# Schematic_v51.net
KiCad netlist of a schematic drawn in EAGLE
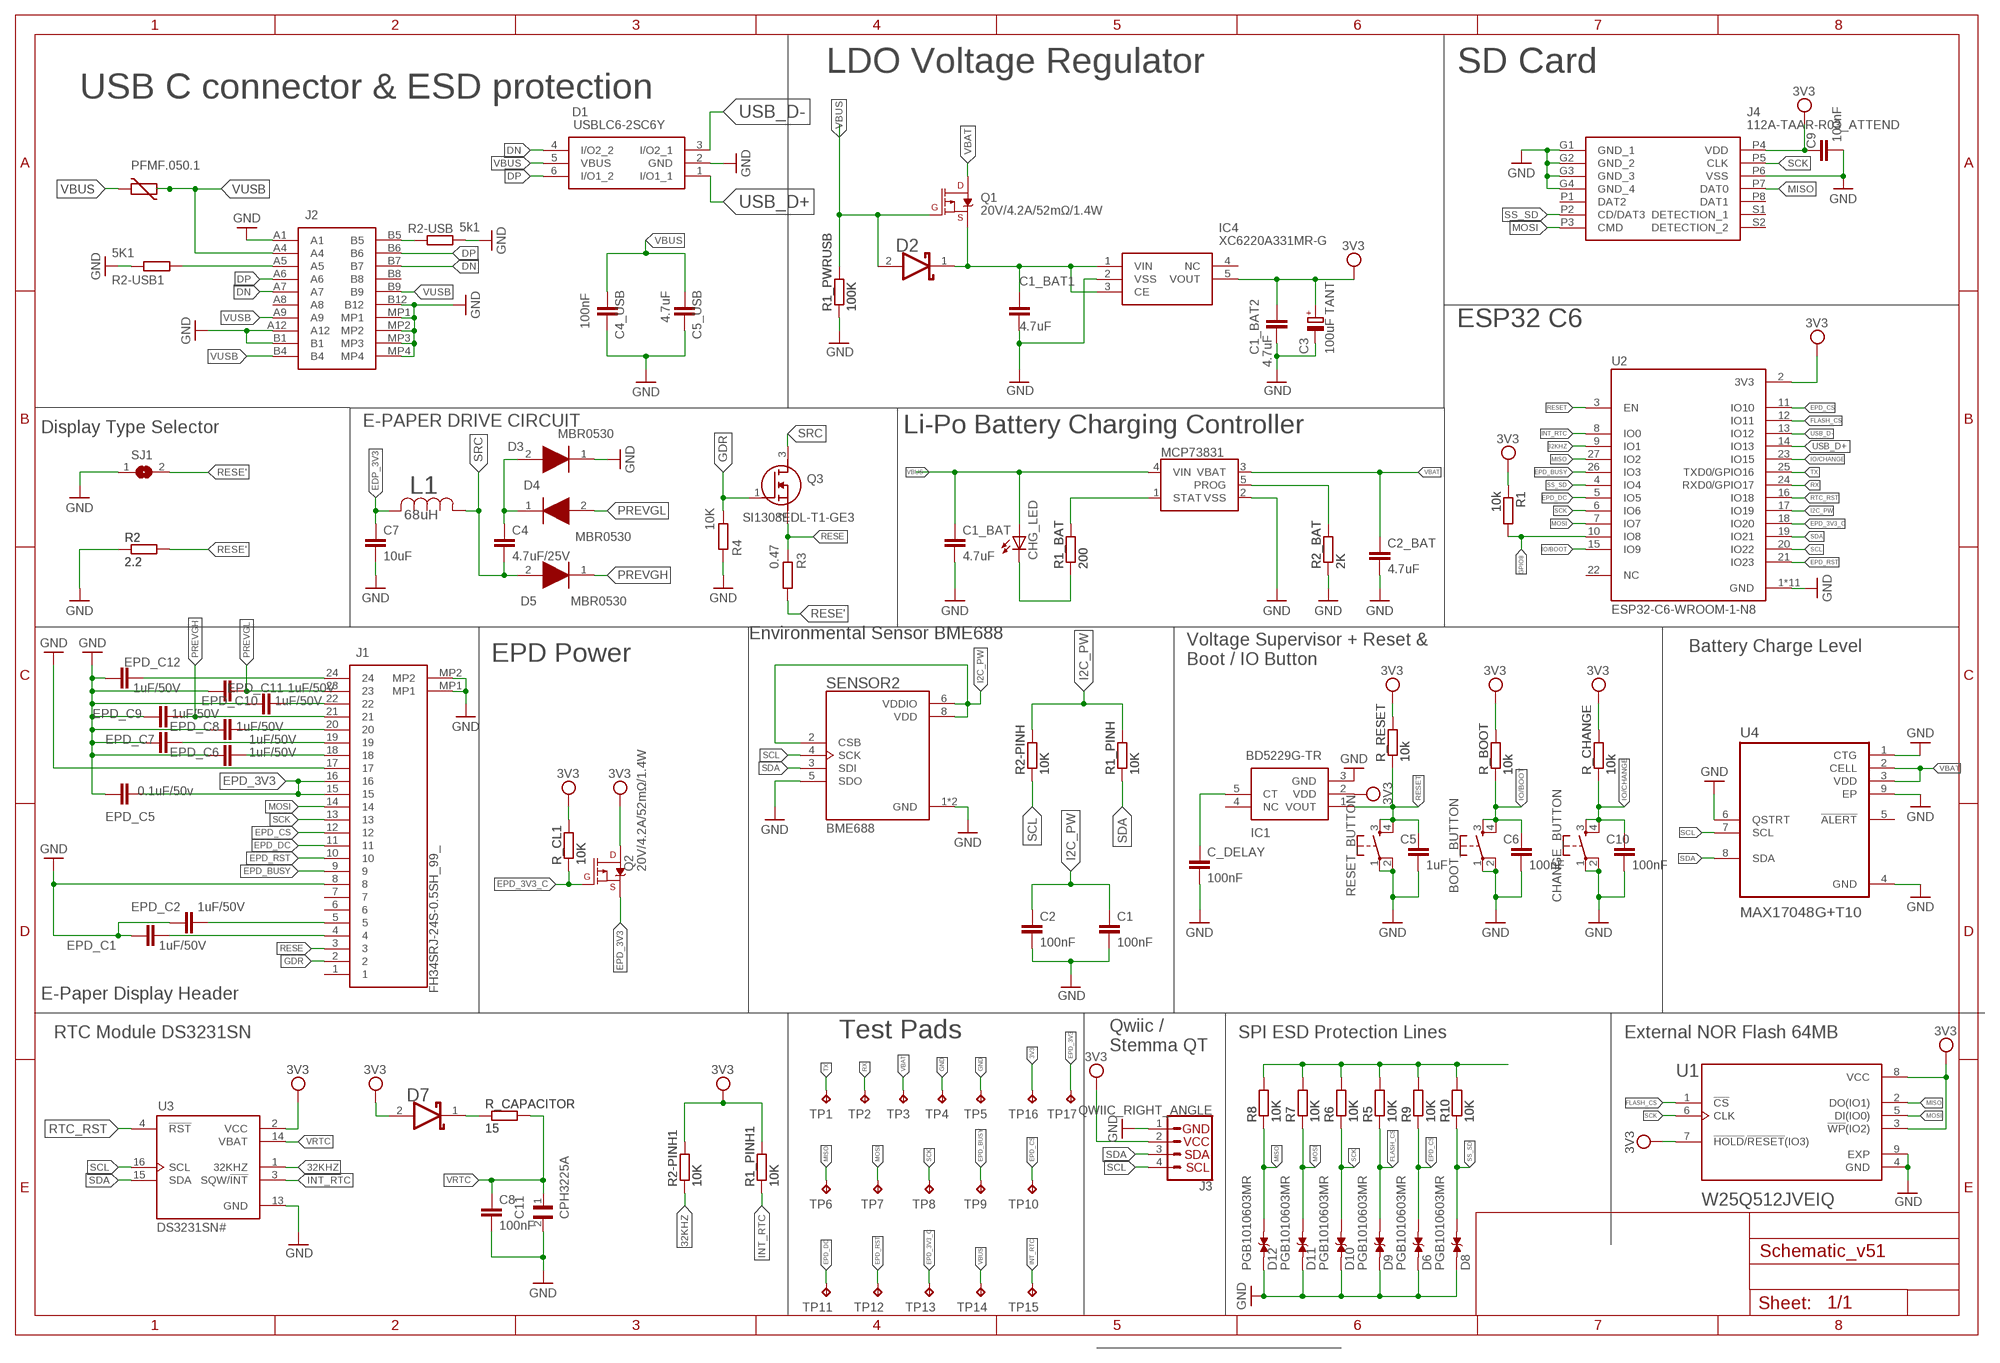
[diagram p0: schematic, sheet 1]

(export (version "E")
  (design (tool "Eeschema 10.0.6"))
  (components
    (comp (ref "BOOT_BUTTON")
      (value "BUTTON_CUSYOMV1")
      (footprint "eagle-import:MYBUTTON")
      (libsource (lib "eagle-import") (part "BUTTON_CUSYOMV1"))
    )
    (comp (ref "C1")
      (value "100nF")
      (footprint "eagle-import:EAGLE-LTSPICE_C0402")
      (libsource (lib "eagle-import") (part "EAGLE-LTSPICE_CC0402"))
    )
    (comp (ref "C1_BAT")
      (value "4.7uF")
      (footprint "eagle-import:EAGLE-LTSPICE_C0402")
      (libsource (lib "eagle-import") (part "EAGLE-LTSPICE_CC0402"))
    )
    (comp (ref "C1_BAT1")
      (value "4.7uF")
      (footprint "eagle-import:ESP32_WROVER_EAGLE-LTSPICE_C0402")
      (libsource (lib "eagle-import") (part "ESP32_WROVER_EAGLE-LTSPICE_CC0402"))
    )
    (comp (ref "C1_BAT2")
      (value "4.7uF")
      (footprint "eagle-import:ESP32_WROVER_EAGLE-LTSPICE_C0402")
      (libsource (lib "eagle-import") (part "ESP32_WROVER_EAGLE-LTSPICE_CC0402"))
    )
    (comp (ref "C2")
      (value "100nF")
      (footprint "eagle-import:EAGLE-LTSPICE_C0402")
      (libsource (lib "eagle-import") (part "EAGLE-LTSPICE_CC0402"))
    )
    (comp (ref "C2_BAT")
      (value "4.7uF")
      (footprint "eagle-import:EAGLE-LTSPICE_C0402")
      (libsource (lib "eagle-import") (part "EAGLE-LTSPICE_CC0402"))
    )
    (comp (ref "C3")
      (value "100uF TANT")
      (footprint "eagle-import:RCL_CT3528")
      (libsource (lib "eagle-import") (part "RCL_CPOL-EUCT3528"))
    )
    (comp (ref "C4")
      (value "4.7uF/25V")
      (footprint "eagle-import:EAGLE-LTSPICE_C0402")
      (libsource (lib "eagle-import") (part "EAGLE-LTSPICE_CC0402"))
    )
    (comp (ref "C4_USB")
      (value "100nF")
      (footprint "eagle-import:EAGLE-LTSPICE_C0402")
      (libsource (lib "eagle-import") (part "EAGLE-LTSPICE_CC0402"))
    )
    (comp (ref "C5")
      (value "1uF")
      (footprint "eagle-import:EAGLE-LTSPICE_C0402")
      (libsource (lib "eagle-import") (part "EAGLE-LTSPICE_CC0402"))
    )
    (comp (ref "C5_USB")
      (value "4.7uF")
      (footprint "eagle-import:EAGLE-LTSPICE_C0402")
      (libsource (lib "eagle-import") (part "EAGLE-LTSPICE_CC0402"))
    )
    (comp (ref "C6")
      (value "100nF")
      (footprint "eagle-import:EAGLE-LTSPICE_C0402")
      (libsource (lib "eagle-import") (part "EAGLE-LTSPICE_CC0402"))
    )
    (comp (ref "C7")
      (value "10uF")
      (footprint "eagle-import:EAGLE-LTSPICE_C0402")
      (libsource (lib "eagle-import") (part "EAGLE-LTSPICE_CC0402"))
    )
    (comp (ref "C8")
      (value "100nF")
      (footprint "eagle-import:EAGLE-LTSPICE_C0402")
      (libsource (lib "eagle-import") (part "EAGLE-LTSPICE_CC0402"))
    )
    (comp (ref "C9")
      (value "100nF")
      (footprint "eagle-import:EAGLE-LTSPICE_C0402")
      (libsource (lib "eagle-import") (part "EAGLE-LTSPICE_CC0402"))
    )
    (comp (ref "C10")
      (value "100nF")
      (footprint "eagle-import:EAGLE-LTSPICE_C0402")
      (libsource (lib "eagle-import") (part "EAGLE-LTSPICE_CC0402"))
    )
    (comp (ref "C11")
      (value "CPH3225A")
      (footprint "eagle-import:CAPCP3225X100N")
      (fields (field (name "MF") "Seiko Instruments"))
      (libsource (lib "eagle-import") (part "CPH3225A"))
    )
    (comp (ref "CHANGE_BUTTON")
      (value "BUTTON_CUSYOMV1")
      (footprint "eagle-import:MYBUTTON")
      (libsource (lib "eagle-import") (part "BUTTON_CUSYOMV1"))
    )
    (comp (ref "CHG_LED")
      (value "ADAFRUIT_LEDCHIP-LED0603")
      (footprint "eagle-import:ADAFRUIT_CHIP-LED0603")
      (libsource (lib "eagle-import") (part "ADAFRUIT_LEDCHIP-LED0603"))
    )
    (comp (ref "C_DELAY")
      (value "100nF")
      (footprint "eagle-import:EAGLE-LTSPICE_C0402")
      (libsource (lib "eagle-import") (part "EAGLE-LTSPICE_CC0402"))
    )
    (comp (ref "D1")
      (value "USBLC6-2SC6Y")
      (footprint "eagle-import:SOT95P280X145-6N")
      (fields (field (name "MF") "STMicroelectronics"))
      (libsource (lib "eagle-import") (part "USBLC6-2SC6Y"))
    )
    (comp (ref "D2")
      (value "ESP32_WROVER_AVX---SD0805S020S1R0_AVX_SD0805S020S1R0_0_0AVX_SD0805S020S1R0_0_0")
      (footprint "eagle-import:ESP32_WROVER_AVX---SD0805S020S1R0_AVX_SD0805S020S1R0_0")
      (fields
        (field (name "DIGIKEY_PART_NUMBER") "478-7800-1-ND")
        (field (name "MF") "AVX")
        (field (name "MOUSER_PART_NUMBER") "581-SD0805S020S1R0")
      )
      (libsource (lib "eagle-import") (part "ESP32_WROVER_AVX---SD0805S020S1R0_AVX_SD0805S020S1R0_0_0AVX_SD0805S020S1R0_0_0"))
    )
    (comp (ref "D3")
      (value "MBR0530")
      (footprint "eagle-import:SOD3716X135N")
      (fields (field (name "MF") "ON Semiconductor"))
      (libsource (lib "eagle-import") (part "MBR0530"))
    )
    (comp (ref "D4")
      (value "MBR0530")
      (footprint "eagle-import:SOD3716X135N")
      (fields (field (name "MF") "ON Semiconductor"))
      (libsource (lib "eagle-import") (part "MBR0530"))
    )
    (comp (ref "D5")
      (value "MBR0530")
      (footprint "eagle-import:SOD3716X135N")
      (fields (field (name "MF") "ON Semiconductor"))
      (libsource (lib "eagle-import") (part "MBR0530"))
    )
    (comp (ref "D6")
      (value "PGB1010603MR")
      (footprint "eagle-import:DIOC1608X36N")
      (fields (field (name "MF") "Littelfuse Inc."))
      (libsource (lib "eagle-import") (part "PGB1010603MR"))
    )
    (comp (ref "D7")
      (value "ESP32_WROVER_AVX---SD0805S020S1R0_AVX_SD0805S020S1R0_0_0AVX_SD0805S020S1R0_0_0")
      (footprint "eagle-import:ESP32_WROVER_AVX---SD0805S020S1R0_AVX_SD0805S020S1R0_0")
      (fields
        (field (name "DIGIKEY_PART_NUMBER") "478-7800-1-ND")
        (field (name "MF") "AVX")
        (field (name "MOUSER_PART_NUMBER") "581-SD0805S020S1R0")
      )
      (libsource (lib "eagle-import") (part "ESP32_WROVER_AVX---SD0805S020S1R0_AVX_SD0805S020S1R0_0_0AVX_SD0805S020S1R0_0_0"))
    )
    (comp (ref "D8")
      (value "PGB1010603MR")
      (footprint "eagle-import:DIOC1608X36N")
      (fields (field (name "MF") "Littelfuse Inc."))
      (libsource (lib "eagle-import") (part "PGB1010603MR"))
    )
    (comp (ref "D9")
      (value "PGB1010603MR")
      (footprint "eagle-import:DIOC1608X36N")
      (fields (field (name "MF") "Littelfuse Inc."))
      (libsource (lib "eagle-import") (part "PGB1010603MR"))
    )
    (comp (ref "D10")
      (value "PGB1010603MR")
      (footprint "eagle-import:DIOC1608X36N")
      (fields (field (name "MF") "Littelfuse Inc."))
      (libsource (lib "eagle-import") (part "PGB1010603MR"))
    )
    (comp (ref "D11")
      (value "PGB1010603MR")
      (footprint "eagle-import:DIOC1608X36N")
      (fields (field (name "MF") "Littelfuse Inc."))
      (libsource (lib "eagle-import") (part "PGB1010603MR"))
    )
    (comp (ref "D12")
      (value "PGB1010603MR")
      (footprint "eagle-import:DIOC1608X36N")
      (fields (field (name "MF") "Littelfuse Inc."))
      (libsource (lib "eagle-import") (part "PGB1010603MR"))
    )
    (comp (ref "EPD_C1")
      (value "1uF/50V")
      (footprint "eagle-import:EAGLE-LTSPICE_C0402")
      (libsource (lib "eagle-import") (part "EAGLE-LTSPICE_CC0402"))
    )
    (comp (ref "EPD_C2")
      (value "1uF/50V")
      (footprint "eagle-import:EAGLE-LTSPICE_C0402")
      (libsource (lib "eagle-import") (part "EAGLE-LTSPICE_CC0402"))
    )
    (comp (ref "EPD_C5")
      (value "0.1uF/50v")
      (footprint "eagle-import:EAGLE-LTSPICE_C0402")
      (libsource (lib "eagle-import") (part "EAGLE-LTSPICE_CC0402"))
    )
    (comp (ref "EPD_C6")
      (value "1uF/50V")
      (footprint "eagle-import:EAGLE-LTSPICE_C0402")
      (libsource (lib "eagle-import") (part "EAGLE-LTSPICE_CC0402"))
    )
    (comp (ref "EPD_C7")
      (value "1uF/50V")
      (footprint "eagle-import:EAGLE-LTSPICE_C0402")
      (libsource (lib "eagle-import") (part "EAGLE-LTSPICE_CC0402"))
    )
    (comp (ref "EPD_C8")
      (value "1uF/50V")
      (footprint "eagle-import:EAGLE-LTSPICE_C0402")
      (libsource (lib "eagle-import") (part "EAGLE-LTSPICE_CC0402"))
    )
    (comp (ref "EPD_C9")
      (value "1uF/50V")
      (footprint "eagle-import:EAGLE-LTSPICE_C0402")
      (libsource (lib "eagle-import") (part "EAGLE-LTSPICE_CC0402"))
    )
    (comp (ref "EPD_C10")
      (value "1uF/50V")
      (footprint "eagle-import:EAGLE-LTSPICE_C0402")
      (libsource (lib "eagle-import") (part "EAGLE-LTSPICE_CC0402"))
    )
    (comp (ref "EPD_C11")
      (value "1uF/50V")
      (footprint "eagle-import:EAGLE-LTSPICE_C0402")
      (libsource (lib "eagle-import") (part "EAGLE-LTSPICE_CC0402"))
    )
    (comp (ref "EPD_C12")
      (value "1uF/50V")
      (footprint "eagle-import:EAGLE-LTSPICE_C0402")
      (libsource (lib "eagle-import") (part "EAGLE-LTSPICE_CC0402"))
    )
    (comp (ref "IC1")
      (value "BD5229G-TR")
      (footprint "eagle-import:SOT95P280X125-5N")
      (fields (field (name "MOUSER_PART_NUMBER") "755-BD5229G-TR"))
      (libsource (lib "eagle-import") (part "BD5229G-TR"))
    )
    (comp (ref "IC4")
      (value "XC6220A331MR-G")
      (footprint "eagle-import:SOT95P280X120-5N")
      (fields (field (name "MOUSER_PART_NUMBER") "865-XC6220A331MR-G"))
      (libsource (lib "eagle-import") (part "XC6220A331MR-G"))
    )
    (comp (ref "J1")
      (value "FH34SRJ-24S-0.5SH_99_")
      (footprint "eagle-import:FH34SRJ24S05SH99")
      (fields
        (field (name "MANUFACTURER_PART_NUMBER") "FH34SRJ-24S-0.5SH(99)")
        (field (name "MOUSER_PART_NUMBER") "798-FH34SRJ24S05SH99")
      )
      (libsource (lib "eagle-import") (part "FH34SRJ-24S-0.5SH_99_"))
    )
    (comp (ref "J2")
      (value "SAMACSYS_PARTS_USB4110-GF-A")
      (footprint "eagle-import:SAMACSYS_PARTS_USB4110GFA")
      (fields
        (field (name "MANUFACTURER_PART_NUMBER") "USB4110-GF-A")
        (field (name "MOUSER_PART_NUMBER") "640-USB4110-GF-A")
      )
      (libsource (lib "eagle-import") (part "SAMACSYS_PARTS_USB4110-GF-A"))
    )
    (comp (ref "J3")
      (value "QWIIC_RIGHT_ANGLE")
      (footprint "eagle-import:JST04_1MM_RA")
      (libsource (lib "eagle-import") (part "QWIIC_CONNECTORJS-1MM"))
    )
    (comp (ref "J4")
      (value "112A-TAAR-R03_ATTEND")
      (footprint "eagle-import:112ATAARR03ATTEND")
      (fields (field (name "MANUFACTURER_PART_NUMBER") "112A-TAAR-R03 ATTEND"))
      (libsource (lib "eagle-import") (part "112A-TAAR-R03_ATTEND"))
    )
    (comp (ref "L1")
      (value "68uH")
      (footprint "eagle-import:IND_4828-WE-TPC_WRE")
      (fields
        (field (name "MANUFACTURER_PART_NUMBER") "744043680")
        (field (name "COPYRIGHT") "Copyright (C) 2024 Ultra Librarian. All rights reserved.")
      )
      (libsource (lib "eagle-import") (part "744043680IND_4828-WE-TPC_WRE"))
    )
    (comp (ref "MCP73831")
      (value "ESP32_WROVER_SPARKFUN-IC-POWER_MCP73831")
      (footprint "eagle-import:ESP32_WROVER_SPARKFUN-IC-POWER_SOT23-5")
      (libsource (lib "eagle-import") (part "ESP32_WROVER_SPARKFUN-IC-POWER_MCP73831"))
    )
    (comp (ref "PFMF.050.1")
      (value "ESP32C6_VARISTORCN1812")
      (footprint "eagle-import:ESP32C6_VARISTOR_CT_CN1812")
      (libsource (lib "eagle-import") (part "ESP32C6_VARISTORCN1812"))
    )
    (comp (ref "Q1")
      (value "20V/4.2A/52mΩ/1.4W")
      (footprint "eagle-import:ESP32_WROVER_SPARKFUN-DISCRETESEMI_SOT23-3")
      (libsource (lib "eagle-import") (part "ESP32_WROVER_SPARKFUN-DISCRETESEMI_MOSFET_PCH-DMG2305UX-7"))
    )
    (comp (ref "Q2")
      (value "20V/4.2A/52mΩ/1.4W")
      (footprint "eagle-import:ESP32_WROVER_SPARKFUN-DISCRETESEMI_SOT23-3")
      (libsource (lib "eagle-import") (part "ESP32_WROVER_SPARKFUN-DISCRETESEMI_MOSFET_PCH-DMG2305UX-7"))
    )
    (comp (ref "Q3")
      (value "SI1308EDL-T1-GE3")
      (footprint "eagle-import:SOT65P210X110-3N")
      (fields (field (name "MF") "Vishay Siliconix"))
      (libsource (lib "eagle-import") (part "SI1308EDL-T1-GE3"))
    )
    (comp (ref "R1")
      (value "10k")
      (footprint "eagle-import:ESP32_WROVER_EAGLE-LTSPICE_R0402")
      (libsource (lib "eagle-import") (part "ESP32_WROVER_EAGLE-LTSPICE_RR0402"))
    )
    (comp (ref "R1_BAT")
      (value "200")
      (footprint "eagle-import:ESP32_WROVER_EAGLE-LTSPICE_R0402")
      (libsource (lib "eagle-import") (part "ESP32_WROVER_EAGLE-LTSPICE_RR0402"))
    )
    (comp (ref "R1_PINH")
      (value "10K")
      (footprint "eagle-import:ESP32_WROVER_EAGLE-LTSPICE_R0402")
      (libsource (lib "eagle-import") (part "ESP32_WROVER_EAGLE-LTSPICE_RR0402"))
    )
    (comp (ref "R1_PINH1")
      (value "10K")
      (footprint "eagle-import:ESP32_WROVER_EAGLE-LTSPICE_R0402")
      (libsource (lib "eagle-import") (part "ESP32_WROVER_EAGLE-LTSPICE_RR0402"))
    )
    (comp (ref "R1_PWRUSB")
      (value "100K")
      (footprint "eagle-import:ESP32_WROVER_EAGLE-LTSPICE_R0402")
      (libsource (lib "eagle-import") (part "ESP32_WROVER_EAGLE-LTSPICE_RR0402"))
    )
    (comp (ref "R2")
      (value "2.2")
      (footprint "eagle-import:ESP32_WROVER_EAGLE-LTSPICE_R0402")
      (libsource (lib "eagle-import") (part "ESP32_WROVER_EAGLE-LTSPICE_RR0402"))
    )
    (comp (ref "R2-PINH")
      (value "10K")
      (footprint "eagle-import:ESP32_WROVER_EAGLE-LTSPICE_R0402")
      (libsource (lib "eagle-import") (part "ESP32_WROVER_EAGLE-LTSPICE_RR0402"))
    )
    (comp (ref "R2-PINH1")
      (value "10K")
      (footprint "eagle-import:ESP32_WROVER_EAGLE-LTSPICE_R0402")
      (libsource (lib "eagle-import") (part "ESP32_WROVER_EAGLE-LTSPICE_RR0402"))
    )
    (comp (ref "R2-USB")
      (value "5k1")
      (footprint "eagle-import:ESP32_WROVER_EAGLE-LTSPICE_R0402")
      (libsource (lib "eagle-import") (part "ESP32_WROVER_EAGLE-LTSPICE_RR0402"))
    )
    (comp (ref "R2-USB1")
      (value "5K1")
      (footprint "eagle-import:ESP32_WROVER_EAGLE-LTSPICE_R0402")
      (fields (field (name "SPICEPREFIX") "R2-USB1"))
      (libsource (lib "eagle-import") (part "ESP32_WROVER_EAGLE-LTSPICE_RR0402"))
    )
    (comp (ref "R2_BAT")
      (value "2K")
      (footprint "eagle-import:ESP32_WROVER_EAGLE-LTSPICE_R0402")
      (libsource (lib "eagle-import") (part "ESP32_WROVER_EAGLE-LTSPICE_RR0402"))
    )
    (comp (ref "R3")
      (value "0.47")
      (footprint "eagle-import:ESP32_WROVER_EAGLE-LTSPICE_R0402")
      (libsource (lib "eagle-import") (part "ESP32_WROVER_EAGLE-LTSPICE_RR0402"))
    )
    (comp (ref "R4")
      (value "10K")
      (footprint "eagle-import:ESP32_WROVER_EAGLE-LTSPICE_R0402")
      (libsource (lib "eagle-import") (part "ESP32_WROVER_EAGLE-LTSPICE_RR0402"))
    )
    (comp (ref "R5")
      (value "10K")
      (footprint "eagle-import:ESP32_WROVER_EAGLE-LTSPICE_R0402")
      (libsource (lib "eagle-import") (part "ESP32_WROVER_EAGLE-LTSPICE_RR0402"))
    )
    (comp (ref "R6")
      (value "10K")
      (footprint "eagle-import:ESP32_WROVER_EAGLE-LTSPICE_R0402")
      (libsource (lib "eagle-import") (part "ESP32_WROVER_EAGLE-LTSPICE_RR0402"))
    )
    (comp (ref "R7")
      (value "10K")
      (footprint "eagle-import:ESP32_WROVER_EAGLE-LTSPICE_R0402")
      (libsource (lib "eagle-import") (part "ESP32_WROVER_EAGLE-LTSPICE_RR0402"))
    )
    (comp (ref "R8")
      (value "10K")
      (footprint "eagle-import:ESP32_WROVER_EAGLE-LTSPICE_R0402")
      (libsource (lib "eagle-import") (part "ESP32_WROVER_EAGLE-LTSPICE_RR0402"))
    )
    (comp (ref "R9")
      (value "10K")
      (footprint "eagle-import:ESP32_WROVER_EAGLE-LTSPICE_R0402")
      (libsource (lib "eagle-import") (part "ESP32_WROVER_EAGLE-LTSPICE_RR0402"))
    )
    (comp (ref "R10")
      (value "10K")
      (footprint "eagle-import:ESP32_WROVER_EAGLE-LTSPICE_R0402")
      (libsource (lib "eagle-import") (part "ESP32_WROVER_EAGLE-LTSPICE_RR0402"))
    )
    (comp (ref "RESET_BUTTON")
      (value "BUTTON_CUSYOMV1")
      (footprint "eagle-import:MYBUTTON")
      (libsource (lib "eagle-import") (part "BUTTON_CUSYOMV1"))
    )
    (comp (ref "R_BOOT")
      (value "10k")
      (footprint "eagle-import:ESP32_WROVER_EAGLE-LTSPICE_R0402")
      (libsource (lib "eagle-import") (part "ESP32_WROVER_EAGLE-LTSPICE_RR0402"))
    )
    (comp (ref "R_CAPACITOR")
      (value "15")
      (footprint "eagle-import:ESP32_WROVER_EAGLE-LTSPICE_R0402")
      (libsource (lib "eagle-import") (part "ESP32_WROVER_EAGLE-LTSPICE_RR0402"))
    )
    (comp (ref "R_CHANGE")
      (value "10k")
      (footprint "eagle-import:ESP32_WROVER_EAGLE-LTSPICE_R0402")
      (libsource (lib "eagle-import") (part "ESP32_WROVER_EAGLE-LTSPICE_RR0402"))
    )
    (comp (ref "R_CL1")
      (value "10K")
      (footprint "eagle-import:ESP32_WROVER_EAGLE-LTSPICE_R0402")
      (libsource (lib "eagle-import") (part "ESP32_WROVER_EAGLE-LTSPICE_RR0402"))
    )
    (comp (ref "R_RESET")
      (value "10k")
      (footprint "eagle-import:ESP32_WROVER_EAGLE-LTSPICE_R0402")
      (libsource (lib "eagle-import") (part "ESP32_WROVER_EAGLE-LTSPICE_RR0402"))
    )
    (comp (ref "SENSOR2")
      (value "ESP32_WROVER_BME680_BME680")
      (footprint "eagle-import:ESP32_WROVER_BME680_PSON80P300X300X100-8N")
      (fields (field (name "MF") "Bosch Sensortec") (field (name "MP") "BME680"))
      (libsource (lib "eagle-import") (part "ESP32_WROVER_BME680_BME680"))
    )
    (comp (ref "SJ1") (value "SJ") (footprint "eagle-import:SJ") (libsource (lib "eagle-import") (part "SJ")))
    (comp (ref "TP1")
      (value "TPTP20R")
      (footprint "eagle-import:TP20R")
      (libsource (lib "eagle-import") (part "TPTP20R"))
    )
    (comp (ref "TP2")
      (value "TPTP20R")
      (footprint "eagle-import:TP20R")
      (libsource (lib "eagle-import") (part "TPTP20R"))
    )
    (comp (ref "TP3")
      (value "TPTP20R")
      (footprint "eagle-import:TP20R")
      (libsource (lib "eagle-import") (part "TPTP20R"))
    )
    (comp (ref "TP4")
      (value "TPTP20R")
      (footprint "eagle-import:TP20R")
      (libsource (lib "eagle-import") (part "TPTP20R"))
    )
    (comp (ref "TP5")
      (value "TPTP20R")
      (footprint "eagle-import:TP20R")
      (libsource (lib "eagle-import") (part "TPTP20R"))
    )
    (comp (ref "TP6")
      (value "TPTP20R")
      (footprint "eagle-import:TP20R")
      (libsource (lib "eagle-import") (part "TPTP20R"))
    )
    (comp (ref "TP7")
      (value "TPTP20R")
      (footprint "eagle-import:TP20R")
      (libsource (lib "eagle-import") (part "TPTP20R"))
    )
    (comp (ref "TP8")
      (value "TPTP20R")
      (footprint "eagle-import:TP20R")
      (libsource (lib "eagle-import") (part "TPTP20R"))
    )
    (comp (ref "TP9")
      (value "TPTP20R")
      (footprint "eagle-import:TP20R")
      (libsource (lib "eagle-import") (part "TPTP20R"))
    )
    (comp (ref "TP10")
      (value "TPTP20R")
      (footprint "eagle-import:TP20R")
      (libsource (lib "eagle-import") (part "TPTP20R"))
    )
    (comp (ref "TP11")
      (value "TPTP20R")
      (footprint "eagle-import:TP20R")
      (libsource (lib "eagle-import") (part "TPTP20R"))
    )
    (comp (ref "TP12")
      (value "TPTP20R")
      (footprint "eagle-import:TP20R")
      (libsource (lib "eagle-import") (part "TPTP20R"))
    )
    (comp (ref "TP13")
      (value "TPTP20R")
      (footprint "eagle-import:TP20R")
      (libsource (lib "eagle-import") (part "TPTP20R"))
    )
    (comp (ref "TP14")
      (value "TPTP20R")
      (footprint "eagle-import:TP20R")
      (libsource (lib "eagle-import") (part "TPTP20R"))
    )
    (comp (ref "TP15")
      (value "TPTP20R")
      (footprint "eagle-import:TP20R")
      (libsource (lib "eagle-import") (part "TPTP20R"))
    )
    (comp (ref "TP16")
      (value "TPTP20R")
      (footprint "eagle-import:TP20R")
      (libsource (lib "eagle-import") (part "TPTP20R"))
    )
    (comp (ref "TP17")
      (value "TPTP20R")
      (footprint "eagle-import:TP20R")
      (libsource (lib "eagle-import") (part "TPTP20R"))
    )
    (comp (ref "U1")
      (value "W25Q512JVEIQ")
      (footprint "eagle-import:SON127P600X800X80-9N")
      (fields (field (name "MF") "Winbond Electronics"))
      (libsource (lib "eagle-import") (part "W25Q512JVEIQ"))
    )
    (comp (ref "U2")
      (value "ESP32-C6-WROOM-1-N8")
      (footprint "eagle-import:XCVR_ESP32-C6-WROOM-1-N8")
      (fields (field (name "MF") "Espressif Systems"))
      (libsource (lib "eagle-import") (part "ESP32-C6-WROOM-1-N8"))
    )
    (comp (ref "U3")
      (value "DS3231SN#")
      (footprint "eagle-import:SOIC127P1032X265-16N")
      (fields (field (name "MF") "Analog Devices"))
      (libsource (lib "eagle-import") (part "DS3231SN#"))
    )
    (comp (ref "U4")
      (value "MAX17048G+T10")
      (footprint "eagle-import:SON50P200X200X80-9N")
      (fields (field (name "MF") "Analog Devices"))
      (libsource (lib "eagle-import") (part "MAX17048G+T10"))
    )
  )
  (nets
    (net (code "1") (name "3V3") (class "Default")
      (node (ref "C1_BAT2") (pin "1") (pinfunction "1_1") (pintype "passive"))
      (node (ref "C3") (pin "+") (pinfunction "+_+") (pintype "passive"))
      (node (ref "C9") (pin "2") (pinfunction "2_2") (pintype "passive"))
      (node (ref "D7") (pin "2") (pinfunction "ANODE_2") (pintype "bidirectional"))
      (node (ref "IC1") (pin "2") (pinfunction "VDD_2") (pintype "bidirectional"))
      (node (ref "IC4") (pin "5") (pinfunction "VOUT_5") (pintype "bidirectional"))
      (node (ref "J3") (pin "2") (pinfunction "2_2") (pintype "power_in"))
      (node (ref "J4") (pin "P4") (pinfunction "VDD_P4") (pintype "bidirectional"))
      (node (ref "Q2") (pin "3") (pinfunction "D_3") (pintype "bidirectional"))
      (node (ref "R1") (pin "1") (pinfunction "1_1") (pintype "passive"))
      (node (ref "R1_PINH1") (pin "2") (pinfunction "2_2") (pintype "passive"))
      (node (ref "R2-PINH1") (pin "2") (pinfunction "2_2") (pintype "passive"))
      (node (ref "R_BOOT") (pin "2") (pinfunction "2_2") (pintype "passive"))
      (node (ref "R_CHANGE") (pin "2") (pinfunction "2_2") (pintype "passive"))
      (node (ref "R_CL1") (pin "2") (pinfunction "2_2") (pintype "passive"))
      (node (ref "R_RESET") (pin "2") (pinfunction "2_2") (pintype "passive"))
      (node (ref "TP16") (pin "TP") (pinfunction "TP_TP") (pintype "input"))
      (node (ref "U1") (pin "3") (pinfunction "~{WP}(IO2)_3") (pintype "bidirectional"))
      (node (ref "U1") (pin "7") (pinfunction "~{HOLD}/~{RESET}(IO3)_7") (pintype "bidirectional"))
      (node (ref "U1") (pin "8") (pinfunction "VCC_8") (pintype "power_in"))
      (node (ref "U2") (pin "2") (pinfunction "3V3_2") (pintype "power_in"))
      (node (ref "U3") (pin "2") (pinfunction "VCC_2") (pintype "power_in"))
    )
    (net (code "2") (name "32KHZ") (class "Default")
      (node (ref "R2-PINH1") (pin "1") (pinfunction "1_1") (pintype "passive"))
      (node (ref "U2") (pin "9") (pinfunction "IO1_9") (pintype "bidirectional"))
      (node (ref "U3") (pin "1") (pinfunction "32KHZ_1") (pintype "output"))
    )
    (net (code "3") (name "DN") (class "Default")
      (node (ref "D1") (pin "4") (pinfunction "I/O2_2_4") (pintype "bidirectional"))
      (node (ref "J2") (pin "A7") (pinfunction "A7_A7") (pintype "bidirectional"))
      (node (ref "J2") (pin "B7") (pinfunction "B7_B7") (pintype "bidirectional"))
    )
    (net (code "4") (name "DP") (class "Default")
      (node (ref "D1") (pin "6") (pinfunction "I/O1_2_6") (pintype "bidirectional"))
      (node (ref "J2") (pin "A6") (pinfunction "A6_A6") (pintype "bidirectional"))
      (node (ref "J2") (pin "B6") (pinfunction "B6_B6") (pintype "bidirectional"))
    )
    (net (code "5") (name "EDP_3V3") (class "Default")
      (node (ref "C7") (pin "1") (pinfunction "1_1") (pintype "passive"))
      (node (ref "L1") (pin "2") (pinfunction "2_2") (pintype "passive"))
    )
    (net (code "6") (name "EPD_3V3") (class "Default")
      (node (ref "EPD_C5") (pin "2") (pinfunction "2_2") (pintype "passive"))
      (node (ref "J1") (pin "15") (pinfunction "15_15") (pintype "bidirectional"))
      (node (ref "J1") (pin "16") (pinfunction "16_16") (pintype "bidirectional"))
      (node (ref "Q2") (pin "2") (pinfunction "S_2") (pintype "bidirectional"))
      (node (ref "TP17") (pin "TP") (pinfunction "TP_TP") (pintype "input"))
    )
    (net (code "7") (name "EPD_3V3_C") (class "Default")
      (node (ref "Q2") (pin "1") (pinfunction "G_1") (pintype "bidirectional"))
      (node (ref "R_CL1") (pin "1") (pinfunction "1_1") (pintype "passive"))
      (node (ref "TP13") (pin "TP") (pinfunction "TP_TP") (pintype "input"))
      (node (ref "U2") (pin "18") (pinfunction "IO20_18") (pintype "bidirectional"))
    )
    (net (code "8") (name "EPD_BUSY") (class "Default")
      (node (ref "J1") (pin "9") (pinfunction "9_9") (pintype "bidirectional"))
      (node (ref "TP9") (pin "TP") (pinfunction "TP_TP") (pintype "input"))
      (node (ref "U2") (pin "26") (pinfunction "IO3_26") (pintype "bidirectional"))
    )
    (net (code "9") (name "EPD_CS") (class "Default")
      (node (ref "D6") (pin "2") (pinfunction "2_2") (pintype "passive"))
      (node (ref "J1") (pin "12") (pinfunction "12_12") (pintype "bidirectional"))
      (node (ref "R9") (pin "1") (pinfunction "1_1") (pintype "passive"))
      (node (ref "TP10") (pin "TP") (pinfunction "TP_TP") (pintype "input"))
      (node (ref "U2") (pin "11") (pinfunction "IO10_11") (pintype "bidirectional"))
    )
    (net (code "10") (name "EPD_DC") (class "Default")
      (node (ref "J1") (pin "11") (pinfunction "11_11") (pintype "bidirectional"))
      (node (ref "TP11") (pin "TP") (pinfunction "TP_TP") (pintype "input"))
      (node (ref "U2") (pin "5") (pinfunction "IO5_5") (pintype "bidirectional"))
    )
    (net (code "11") (name "EPD_RST") (class "Default")
      (node (ref "J1") (pin "10") (pinfunction "10_10") (pintype "bidirectional"))
      (node (ref "TP12") (pin "TP") (pinfunction "TP_TP") (pintype "input"))
      (node (ref "U2") (pin "21") (pinfunction "IO23_21") (pintype "bidirectional"))
    )
    (net (code "12") (name "FLASH_CS") (class "Default")
      (node (ref "D9") (pin "2") (pinfunction "2_2") (pintype "passive"))
      (node (ref "R5") (pin "1") (pinfunction "1_1") (pintype "passive"))
      (node (ref "U1") (pin "1") (pinfunction "~{CS}_1") (pintype "input"))
      (node (ref "U2") (pin "12") (pinfunction "IO11_12") (pintype "bidirectional"))
    )
    (net (code "13") (name "GDR") (class "Default")
      (node (ref "J1") (pin "2") (pinfunction "2_2") (pintype "bidirectional"))
      (node (ref "Q3") (pin "1") (pinfunction "G_1") (pintype "bidirectional"))
      (node (ref "R4") (pin "2") (pinfunction "2_2") (pintype "passive"))
    )
    (net (code "14") (name "GND") (class "Default")
      (node (ref "BOOT_BUTTON") (pin "1") (pinfunction "1_1") (pintype "passive"))
      (node (ref "BOOT_BUTTON") (pin "2") (pinfunction "2_2") (pintype "passive"))
      (node (ref "C1") (pin "2") (pinfunction "2_2") (pintype "passive"))
      (node (ref "C10") (pin "2") (pinfunction "2_2") (pintype "passive"))
      (node (ref "C11") (pin "2") (pinfunction "2_2") (pintype "passive"))
      (node (ref "C1_BAT") (pin "2") (pinfunction "2_2") (pintype "passive"))
      (node (ref "C1_BAT1") (pin "2") (pinfunction "2_2") (pintype "passive"))
      (node (ref "C1_BAT2") (pin "2") (pinfunction "2_2") (pintype "passive"))
      (node (ref "C2") (pin "2") (pinfunction "2_2") (pintype "passive"))
      (node (ref "C2_BAT") (pin "2") (pinfunction "2_2") (pintype "passive"))
      (node (ref "C3") (pin "-") (pinfunction "-_-") (pintype "passive"))
      (node (ref "C4_USB") (pin "2") (pinfunction "2_2") (pintype "passive"))
      (node (ref "C5") (pin "2") (pinfunction "2_2") (pintype "passive"))
      (node (ref "C5_USB") (pin "2") (pinfunction "2_2") (pintype "passive"))
      (node (ref "C6") (pin "2") (pinfunction "2_2") (pintype "passive"))
      (node (ref "C7") (pin "2") (pinfunction "2_2") (pintype "passive"))
      (node (ref "C8") (pin "2") (pinfunction "2_2") (pintype "passive"))
      (node (ref "C9") (pin "1") (pinfunction "1_1") (pintype "passive"))
      (node (ref "CHANGE_BUTTON") (pin "1") (pinfunction "1_1") (pintype "passive"))
      (node (ref "CHANGE_BUTTON") (pin "2") (pinfunction "2_2") (pintype "passive"))
      (node (ref "C_DELAY") (pin "2") (pinfunction "2_2") (pintype "passive"))
      (node (ref "D1") (pin "2") (pinfunction "GND_2") (pintype "bidirectional"))
      (node (ref "D10") (pin "1") (pinfunction "1_1") (pintype "passive"))
      (node (ref "D11") (pin "1") (pinfunction "1_1") (pintype "passive"))
      (node (ref "D12") (pin "1") (pinfunction "1_1") (pintype "passive"))
      (node (ref "D3") (pin "1") (pinfunction "K_1") (pintype "bidirectional"))
      (node (ref "D6") (pin "1") (pinfunction "1_1") (pintype "passive"))
      (node (ref "D8") (pin "1") (pinfunction "1_1") (pintype "passive"))
      (node (ref "D9") (pin "1") (pinfunction "1_1") (pintype "passive"))
      (node (ref "EPD_C1") (pin "1") (pinfunction "1_1") (pintype "passive"))
      (node (ref "EPD_C10") (pin "1") (pinfunction "1_1") (pintype "passive"))
      (node (ref "EPD_C11") (pin "1") (pinfunction "1_1") (pintype "passive"))
      (node (ref "EPD_C12") (pin "1") (pinfunction "1_1") (pintype "passive"))
      (node (ref "EPD_C2") (pin "1") (pinfunction "1_1") (pintype "passive"))
      (node (ref "EPD_C5") (pin "1") (pinfunction "1_1") (pintype "passive"))
      (node (ref "EPD_C6") (pin "1") (pinfunction "1_1") (pintype "passive"))
      (node (ref "EPD_C7") (pin "1") (pinfunction "1_1") (pintype "passive"))
      (node (ref "EPD_C8") (pin "1") (pinfunction "1_1") (pintype "passive"))
      (node (ref "EPD_C9") (pin "1") (pinfunction "1_1") (pintype "passive"))
      (node (ref "IC1") (pin "3") (pinfunction "GND_3") (pintype "bidirectional"))
      (node (ref "IC4") (pin "2") (pinfunction "VSS_2") (pintype "bidirectional"))
      (node (ref "J1") (pin "17") (pinfunction "17_17") (pintype "bidirectional"))
      (node (ref "J1") (pin "8") (pinfunction "8_8") (pintype "bidirectional"))
      (node (ref "J1") (pin "MP1") (pinfunction "MP1_MP1") (pintype "bidirectional"))
      (node (ref "J1") (pin "MP2") (pinfunction "MP2_MP2") (pintype "bidirectional"))
      (node (ref "J2") (pin "A1") (pinfunction "A1_A1") (pintype "bidirectional"))
      (node (ref "J2") (pin "A12") (pinfunction "A12_A12") (pintype "bidirectional"))
      (node (ref "J2") (pin "B1") (pinfunction "B1_B1") (pintype "bidirectional"))
      (node (ref "J2") (pin "B12") (pinfunction "B12_B12") (pintype "bidirectional"))
      (node (ref "J2") (pin "MP1") (pinfunction "MP1_MP1") (pintype "bidirectional"))
      (node (ref "J2") (pin "MP2") (pinfunction "MP2_MP2") (pintype "bidirectional"))
      (node (ref "J2") (pin "MP3") (pinfunction "MP3_MP3") (pintype "bidirectional"))
      (node (ref "J2") (pin "MP4") (pinfunction "MP4_MP4") (pintype "bidirectional"))
      (node (ref "J3") (pin "1") (pinfunction "1_1") (pintype "power_in"))
      (node (ref "J4") (pin "G1") (pinfunction "GND_1_G1") (pintype "bidirectional"))
      (node (ref "J4") (pin "G2") (pinfunction "GND_2_G2") (pintype "bidirectional"))
      (node (ref "J4") (pin "G3") (pinfunction "GND_3_G3") (pintype "bidirectional"))
      (node (ref "J4") (pin "G4") (pinfunction "GND_4_G4") (pintype "bidirectional"))
      (node (ref "J4") (pin "P6") (pinfunction "VSS_P6") (pintype "bidirectional"))
      (node (ref "MCP73831") (pin "2") (pinfunction "VSS_2") (pintype "power_in"))
      (node (ref "R1_PWRUSB") (pin "1") (pinfunction "1_1") (pintype "passive"))
      (node (ref "R2") (pin "1") (pinfunction "1_1") (pintype "passive"))
      (node (ref "R2-USB") (pin "2") (pinfunction "2_2") (pintype "passive"))
      (node (ref "R2-USB1") (pin "1") (pinfunction "1_1") (pintype "passive"))
      (node (ref "R2_BAT") (pin "1") (pinfunction "1_1") (pintype "passive"))
      (node (ref "R4") (pin "1") (pinfunction "1_1") (pintype "passive"))
      (node (ref "RESET_BUTTON") (pin "1") (pinfunction "1_1") (pintype "passive"))
      (node (ref "RESET_BUTTON") (pin "2") (pinfunction "2_2") (pintype "passive"))
      (node (ref "SENSOR2") (pin "1") (pinfunction "GND_1") (pintype "power_in"))
      (node (ref "SENSOR2") (pin "5") (pinfunction "SDO_5") (pintype "bidirectional"))
      (node (ref "SENSOR2") (pin "7") (pinfunction "GND_7") (pintype "power_in"))
      (node (ref "SJ1") (pin "1") (pinfunction "1_1") (pintype "passive"))
      (node (ref "TP4") (pin "TP") (pinfunction "TP_TP") (pintype "input"))
      (node (ref "TP5") (pin "TP") (pinfunction "TP_TP") (pintype "input"))
      (node (ref "U1") (pin "4") (pinfunction "GND_4") (pintype "power_in"))
      (node (ref "U1") (pin "9") (pinfunction "EXP_9") (pintype "passive"))
      (node (ref "U2") (pin "1") (pinfunction "GND_1") (pintype "power_in"))
      (node (ref "U2") (pin "28") (pinfunction "GND_28") (pintype "power_in"))
      (node (ref "U2") (pin "29_1") (pinfunction "GND_29_1") (pintype "power_in"))
      (node (ref "U2") (pin "29_2") (pinfunction "GND_29_2") (pintype "power_in"))
      (node (ref "U2") (pin "29_3") (pinfunction "GND_29_3") (pintype "power_in"))
      (node (ref "U2") (pin "29_4") (pinfunction "GND_29_4") (pintype "power_in"))
      (node (ref "U2") (pin "29_5") (pinfunction "GND_29_5") (pintype "power_in"))
      (node (ref "U2") (pin "29_6") (pinfunction "GND_29_6") (pintype "power_in"))
      (node (ref "U2") (pin "29_7") (pinfunction "GND_29_7") (pintype "power_in"))
      (node (ref "U2") (pin "29_8") (pinfunction "GND_29_8") (pintype "power_in"))
      (node (ref "U2") (pin "29_9") (pinfunction "GND_29_9") (pintype "power_in"))
      (node (ref "U3") (pin "13") (pinfunction "GND_13") (pintype "power_in"))
      (node (ref "U4") (pin "1") (pinfunction "CTG_1") (pintype "power_in"))
      (node (ref "U4") (pin "4") (pinfunction "GND_4") (pintype "power_in"))
      (node (ref "U4") (pin "6") (pinfunction "QSTRT_6") (pintype "input"))
      (node (ref "U4") (pin "9") (pinfunction "EP_9") (pintype "power_in"))
    )
    (net (code "15") (name "GPIO8") (class "Default")
      (node (ref "R1") (pin "2") (pinfunction "2_2") (pintype "passive"))
      (node (ref "U2") (pin "10") (pinfunction "IO8_10") (pintype "bidirectional"))
    )
    (net (code "16") (name "I2C_PW") (class "Default")
      (node (ref "C1") (pin "1") (pinfunction "1_1") (pintype "passive"))
      (node (ref "C2") (pin "1") (pinfunction "1_1") (pintype "passive"))
      (node (ref "R1_PINH") (pin "2") (pinfunction "2_2") (pintype "passive"))
      (node (ref "R2-PINH") (pin "2") (pinfunction "2_2") (pintype "passive"))
      (node (ref "SENSOR2") (pin "2") (pinfunction "CSB_2") (pintype "input"))
      (node (ref "SENSOR2") (pin "6") (pinfunction "VDDIO_6") (pintype "power_in"))
      (node (ref "SENSOR2") (pin "8") (pinfunction "VDD_8") (pintype "power_in"))
      (node (ref "U2") (pin "17") (pinfunction "IO19_17") (pintype "bidirectional"))
    )
    (net (code "17") (name "INT_RTC") (class "Default")
      (node (ref "R1_PINH1") (pin "1") (pinfunction "1_1") (pintype "passive"))
      (node (ref "TP15") (pin "TP") (pinfunction "TP_TP") (pintype "input"))
      (node (ref "U2") (pin "8") (pinfunction "IO0_8") (pintype "bidirectional"))
      (node (ref "U3") (pin "3") (pinfunction "SQW/~{INT}_3") (pintype "output"))
    )
    (net (code "18") (name "IO{slash}BOOT") (class "Default")
      (node (ref "BOOT_BUTTON") (pin "3") (pinfunction "3_3") (pintype "passive"))
      (node (ref "BOOT_BUTTON") (pin "4") (pinfunction "4_4") (pintype "passive"))
      (node (ref "C6") (pin "1") (pinfunction "1_1") (pintype "passive"))
      (node (ref "R_BOOT") (pin "1") (pinfunction "1_1") (pintype "passive"))
      (node (ref "U2") (pin "15") (pinfunction "IO9_15") (pintype "bidirectional"))
    )
    (net (code "19") (name "IO{slash}CHANGE") (class "Default")
      (node (ref "C10") (pin "1") (pinfunction "1_1") (pintype "passive"))
      (node (ref "CHANGE_BUTTON") (pin "3") (pinfunction "3_3") (pintype "passive"))
      (node (ref "CHANGE_BUTTON") (pin "4") (pinfunction "4_4") (pintype "passive"))
      (node (ref "R_CHANGE") (pin "1") (pinfunction "1_1") (pintype "passive"))
      (node (ref "U2") (pin "23") (pinfunction "IO15_23") (pintype "bidirectional"))
    )
    (net (code "20") (name "MISO") (class "Default")
      (node (ref "D12") (pin "2") (pinfunction "2_2") (pintype "passive"))
      (node (ref "J4") (pin "P7") (pinfunction "DAT0_P7") (pintype "bidirectional"))
      (node (ref "R8") (pin "1") (pinfunction "1_1") (pintype "passive"))
      (node (ref "TP6") (pin "TP") (pinfunction "TP_TP") (pintype "input"))
      (node (ref "U1") (pin "2") (pinfunction "DO(IO1)_2") (pintype "bidirectional"))
      (node (ref "U2") (pin "27") (pinfunction "IO2_27") (pintype "bidirectional"))
    )
    (net (code "21") (name "MOSI") (class "Default")
      (node (ref "D11") (pin "2") (pinfunction "2_2") (pintype "passive"))
      (node (ref "J1") (pin "14") (pinfunction "14_14") (pintype "bidirectional"))
      (node (ref "J4") (pin "P3") (pinfunction "CMD_P3") (pintype "bidirectional"))
      (node (ref "R7") (pin "1") (pinfunction "1_1") (pintype "passive"))
      (node (ref "TP7") (pin "TP") (pinfunction "TP_TP") (pintype "input"))
      (node (ref "U1") (pin "5") (pinfunction "DI(IO0)_5") (pintype "bidirectional"))
      (node (ref "U2") (pin "7") (pinfunction "IO7_7") (pintype "bidirectional"))
    )
    (net (code "22") (name "Net-(CHG_LED-PadC)") (class "Default")
      (node (ref "CHG_LED") (pin "C") (pinfunction "C_C") (pintype "passive"))
      (node (ref "R1_BAT") (pin "1") (pinfunction "1_1") (pintype "passive"))
    )
    (net (code "23") (name "Net-(D2-CATHODE)") (class "Default")
      (node (ref "C1_BAT1") (pin "1") (pinfunction "1_1") (pintype "passive"))
      (node (ref "D2") (pin "1") (pinfunction "CATHODE_1") (pintype "bidirectional"))
      (node (ref "IC4") (pin "1") (pinfunction "VIN_1") (pintype "bidirectional"))
      (node (ref "IC4") (pin "3") (pinfunction "CE_3") (pintype "bidirectional"))
      (node (ref "Q1") (pin "2") (pinfunction "S_2") (pintype "bidirectional"))
    )
    (net (code "24") (name "Net-(D3-A)") (class "Default")
      (node (ref "C4") (pin "1") (pinfunction "1_1") (pintype "passive"))
      (node (ref "D3") (pin "2") (pinfunction "A_2") (pintype "bidirectional"))
      (node (ref "D4") (pin "1") (pinfunction "K_1") (pintype "bidirectional"))
    )
    (net (code "25") (name "Net-(D7-CATHODE)") (class "Default")
      (node (ref "D7") (pin "1") (pinfunction "CATHODE_1") (pintype "bidirectional"))
      (node (ref "R_CAPACITOR") (pin "1") (pinfunction "1_1") (pintype "passive"))
    )
    (net (code "26") (name "Net-(EPD_C1-Pad2)") (class "Default")
      (node (ref "EPD_C1") (pin "2") (pinfunction "2_2") (pintype "passive"))
      (node (ref "J1") (pin "4") (pinfunction "4_4") (pintype "bidirectional"))
    )
    (net (code "27") (name "Net-(EPD_C2-Pad2)") (class "Default")
      (node (ref "EPD_C2") (pin "2") (pinfunction "2_2") (pintype "passive"))
      (node (ref "J1") (pin "5") (pinfunction "5_5") (pintype "bidirectional"))
    )
    (net (code "28") (name "Net-(EPD_C6-Pad2)") (class "Default")
      (node (ref "EPD_C6") (pin "2") (pinfunction "2_2") (pintype "passive"))
      (node (ref "J1") (pin "18") (pinfunction "18_18") (pintype "bidirectional"))
    )
    (net (code "29") (name "Net-(EPD_C7-Pad2)") (class "Default")
      (node (ref "EPD_C7") (pin "2") (pinfunction "2_2") (pintype "passive"))
      (node (ref "J1") (pin "19") (pinfunction "19_19") (pintype "bidirectional"))
    )
    (net (code "30") (name "Net-(EPD_C8-Pad2)") (class "Default")
      (node (ref "EPD_C8") (pin "2") (pinfunction "2_2") (pintype "passive"))
      (node (ref "J1") (pin "20") (pinfunction "20_20") (pintype "bidirectional"))
    )
    (net (code "31") (name "Net-(EPD_C10-Pad2)") (class "Default")
      (node (ref "EPD_C10") (pin "2") (pinfunction "2_2") (pintype "passive"))
      (node (ref "J1") (pin "22") (pinfunction "22_22") (pintype "bidirectional"))
    )
    (net (code "32") (name "Net-(EPD_C12-Pad2)") (class "Default")
      (node (ref "EPD_C12") (pin "2") (pinfunction "2_2") (pintype "passive"))
      (node (ref "J1") (pin "24") (pinfunction "24_24") (pintype "bidirectional"))
    )
    (net (code "33") (name "Net-(IC1-CT)") (class "Default")
      (node (ref "C_DELAY") (pin "1") (pinfunction "1_1") (pintype "passive"))
      (node (ref "IC1") (pin "5") (pinfunction "CT_5") (pintype "bidirectional"))
    )
    (net (code "34") (name "Net-(J2-PadA5)") (class "Default")
      (node (ref "J2") (pin "A5") (pinfunction "A5_A5") (pintype "bidirectional"))
      (node (ref "R2-USB1") (pin "2") (pinfunction "2_2") (pintype "passive"))
    )
    (net (code "35") (name "Net-(J2-PadB5)") (class "Default")
      (node (ref "J2") (pin "B5") (pinfunction "B5_B5") (pintype "bidirectional"))
      (node (ref "R2-USB") (pin "1") (pinfunction "1_1") (pintype "passive"))
    )
    (net (code "36") (name "Net-(MCP73831-PROG)") (class "Default")
      (node (ref "MCP73831") (pin "5") (pinfunction "PROG_5") (pintype "input"))
      (node (ref "R2_BAT") (pin "2") (pinfunction "2_2") (pintype "passive"))
    )
    (net (code "37") (name "Net-(MCP73831-STAT)") (class "Default")
      (node (ref "MCP73831") (pin "1") (pinfunction "STAT_1") (pintype "output"))
      (node (ref "R1_BAT") (pin "2") (pinfunction "2_2") (pintype "passive"))
    )
    (net (code "38") (name "Net-(R10-Pad2)") (class "Default")
      (node (ref "R10") (pin "2") (pinfunction "2_2") (pintype "passive"))
      (node (ref "R5") (pin "2") (pinfunction "2_2") (pintype "passive"))
      (node (ref "R6") (pin "2") (pinfunction "2_2") (pintype "passive"))
      (node (ref "R7") (pin "2") (pinfunction "2_2") (pintype "passive"))
      (node (ref "R8") (pin "2") (pinfunction "2_2") (pintype "passive"))
      (node (ref "R9") (pin "2") (pinfunction "2_2") (pintype "passive"))
    )
    (net (code "39") (name "PREVGH") (class "Default")
      (node (ref "D5") (pin "1") (pinfunction "K_1") (pintype "bidirectional"))
      (node (ref "EPD_C9") (pin "2") (pinfunction "2_2") (pintype "passive"))
      (node (ref "J1") (pin "21") (pinfunction "21_21") (pintype "bidirectional"))
    )
    (net (code "40") (name "PREVGL") (class "Default")
      (node (ref "D4") (pin "2") (pinfunction "A_2") (pintype "bidirectional"))
      (node (ref "EPD_C11") (pin "2") (pinfunction "2_2") (pintype "passive"))
      (node (ref "J1") (pin "23") (pinfunction "23_23") (pintype "bidirectional"))
    )
    (net (code "41") (name "RESE") (class "Default")
      (node (ref "J1") (pin "3") (pinfunction "3_3") (pintype "bidirectional"))
      (node (ref "Q3") (pin "2") (pinfunction "S_2") (pintype "bidirectional"))
      (node (ref "R3") (pin "2") (pinfunction "2_2") (pintype "passive"))
    )
    (net (code "42") (name "RESE'") (class "Default")
      (node (ref "R2") (pin "2") (pinfunction "2_2") (pintype "passive"))
      (node (ref "R3") (pin "1") (pinfunction "1_1") (pintype "passive"))
      (node (ref "SJ1") (pin "2") (pinfunction "2_2") (pintype "passive"))
    )
    (net (code "43") (name "RESET") (class "Default")
      (node (ref "C5") (pin "1") (pinfunction "1_1") (pintype "passive"))
      (node (ref "IC1") (pin "1") (pinfunction "VOUT_1") (pintype "bidirectional"))
      (node (ref "RESET_BUTTON") (pin "3") (pinfunction "3_3") (pintype "passive"))
      (node (ref "RESET_BUTTON") (pin "4") (pinfunction "4_4") (pintype "passive"))
      (node (ref "R_RESET") (pin "1") (pinfunction "1_1") (pintype "passive"))
      (node (ref "U2") (pin "3") (pinfunction "EN_3") (pintype "input"))
    )
    (net (code "44") (name "RTC_RST") (class "Default")
      (node (ref "U2") (pin "16") (pinfunction "IO18_16") (pintype "bidirectional"))
      (node (ref "U3") (pin "4") (pinfunction "~{RST}_4") (pintype "input"))
    )
    (net (code "45") (name "RX") (class "Default")
      (node (ref "TP2") (pin "TP") (pinfunction "TP_TP") (pintype "input"))
      (node (ref "U2") (pin "24") (pinfunction "RXD0/GPIO17_24") (pintype "bidirectional"))
    )
    (net (code "46") (name "SCK") (class "Default")
      (node (ref "D10") (pin "2") (pinfunction "2_2") (pintype "passive"))
      (node (ref "J1") (pin "13") (pinfunction "13_13") (pintype "bidirectional"))
      (node (ref "J4") (pin "P5") (pinfunction "CLK_P5") (pintype "bidirectional"))
      (node (ref "R6") (pin "1") (pinfunction "1_1") (pintype "passive"))
      (node (ref "TP8") (pin "TP") (pinfunction "TP_TP") (pintype "input"))
      (node (ref "U1") (pin "6") (pinfunction "CLK_6") (pintype "input"))
      (node (ref "U2") (pin "6") (pinfunction "IO6_6") (pintype "bidirectional"))
    )
    (net (code "47") (name "SCL") (class "Default")
      (node (ref "J3") (pin "4") (pinfunction "4_4") (pintype "passive"))
      (node (ref "R2-PINH") (pin "1") (pinfunction "1_1") (pintype "passive"))
      (node (ref "SENSOR2") (pin "4") (pinfunction "SCK_4") (pintype "input"))
      (node (ref "U2") (pin "20") (pinfunction "IO22_20") (pintype "bidirectional"))
      (node (ref "U3") (pin "16") (pinfunction "SCL_16") (pintype "input"))
      (node (ref "U4") (pin "7") (pinfunction "SCL_7") (pintype "input"))
    )
    (net (code "48") (name "SDA") (class "Default")
      (node (ref "J3") (pin "3") (pinfunction "3_3") (pintype "passive"))
      (node (ref "R1_PINH") (pin "1") (pinfunction "1_1") (pintype "passive"))
      (node (ref "SENSOR2") (pin "3") (pinfunction "SDI_3") (pintype "bidirectional"))
      (node (ref "U2") (pin "19") (pinfunction "IO21_19") (pintype "bidirectional"))
      (node (ref "U3") (pin "15") (pinfunction "SDA_15") (pintype "bidirectional"))
      (node (ref "U4") (pin "8") (pinfunction "SDA_8") (pintype "bidirectional"))
    )
    (net (code "49") (name "SRC") (class "Default")
      (node (ref "C4") (pin "2") (pinfunction "2_2") (pintype "passive"))
      (node (ref "D5") (pin "2") (pinfunction "A_2") (pintype "bidirectional"))
      (node (ref "L1") (pin "1") (pinfunction "1_1") (pintype "passive"))
      (node (ref "Q3") (pin "3") (pinfunction "D_3") (pintype "bidirectional"))
    )
    (net (code "50") (name "SS_SD") (class "Default")
      (node (ref "D8") (pin "2") (pinfunction "2_2") (pintype "passive"))
      (node (ref "J4") (pin "P2") (pinfunction "CD/DAT3_P2") (pintype "bidirectional"))
      (node (ref "R10") (pin "1") (pinfunction "1_1") (pintype "passive"))
      (node (ref "U2") (pin "4") (pinfunction "IO4_4") (pintype "bidirectional"))
    )
    (net (code "51") (name "TX") (class "Default")
      (node (ref "TP1") (pin "TP") (pinfunction "TP_TP") (pintype "input"))
      (node (ref "U2") (pin "25") (pinfunction "TXD0/GPIO16_25") (pintype "bidirectional"))
    )
    (net (code "52") (name "USB_D+") (class "Default")
      (node (ref "D1") (pin "1") (pinfunction "I/O1_1_1") (pintype "bidirectional"))
      (node (ref "U2") (pin "14") (pinfunction "IO13_14") (pintype "bidirectional"))
    )
    (net (code "53") (name "USB_D-") (class "Default")
      (node (ref "D1") (pin "3") (pinfunction "I/O2_1_3") (pintype "bidirectional"))
      (node (ref "U2") (pin "13") (pinfunction "IO12_13") (pintype "bidirectional"))
    )
    (net (code "54") (name "VBAT") (class "Default")
      (node (ref "C2_BAT") (pin "1") (pinfunction "1_1") (pintype "passive"))
      (node (ref "MCP73831") (pin "3") (pinfunction "VBAT_3") (pintype "power_in"))
      (node (ref "Q1") (pin "3") (pinfunction "D_3") (pintype "bidirectional"))
      (node (ref "TP3") (pin "TP") (pinfunction "TP_TP") (pintype "input"))
      (node (ref "U4") (pin "2") (pinfunction "CELL_2") (pintype "power_in"))
      (node (ref "U4") (pin "3") (pinfunction "VDD_3") (pintype "power_in"))
    )
    (net (code "55") (name "VBUS") (class "Default")
      (node (ref "C1_BAT") (pin "1") (pinfunction "1_1") (pintype "passive"))
      (node (ref "C4_USB") (pin "1") (pinfunction "1_1") (pintype "passive"))
      (node (ref "C5_USB") (pin "1") (pinfunction "1_1") (pintype "passive"))
      (node (ref "CHG_LED") (pin "A") (pinfunction "A_A") (pintype "passive"))
      (node (ref "D1") (pin "5") (pinfunction "VBUS_5") (pintype "bidirectional"))
      (node (ref "D2") (pin "2") (pinfunction "ANODE_2") (pintype "bidirectional"))
      (node (ref "MCP73831") (pin "4") (pinfunction "VIN_4") (pintype "power_in"))
      (node (ref "PFMF.050.1") (pin "2") (pinfunction "2_2") (pintype "passive"))
      (node (ref "Q1") (pin "1") (pinfunction "G_1") (pintype "bidirectional"))
      (node (ref "R1_PWRUSB") (pin "2") (pinfunction "2_2") (pintype "passive"))
      (node (ref "TP14") (pin "TP") (pinfunction "TP_TP") (pintype "input"))
    )
    (net (code "56") (name "VRTC") (class "Default")
      (node (ref "C11") (pin "1") (pinfunction "1_1") (pintype "passive"))
      (node (ref "C8") (pin "1") (pinfunction "1_1") (pintype "passive"))
      (node (ref "R_CAPACITOR") (pin "2") (pinfunction "2_2") (pintype "passive"))
      (node (ref "U3") (pin "14") (pinfunction "VBAT_14") (pintype "power_in"))
    )
    (net (code "57") (name "VUSB") (class "Default")
      (node (ref "J2") (pin "A4") (pinfunction "A4_A4") (pintype "bidirectional"))
      (node (ref "J2") (pin "A9") (pinfunction "A9_A9") (pintype "bidirectional"))
      (node (ref "J2") (pin "B4") (pinfunction "B4_B4") (pintype "bidirectional"))
      (node (ref "J2") (pin "B9") (pinfunction "B9_B9") (pintype "bidirectional"))
      (node (ref "PFMF.050.1") (pin "1") (pinfunction "1_1") (pintype "passive"))
    )
    (net (code "58") (name "unconnected-(IC1-NC-Pad4)") (class "Default")
      (node (ref "IC1") (pin "4") (pinfunction "NC_4") (pintype "no_connect"))
    )
    (net (code "59") (name "unconnected-(IC4-NC-Pad4)") (class "Default")
      (node (ref "IC4") (pin "4") (pinfunction "NC_4") (pintype "no_connect"))
    )
    (net (code "60") (name "unconnected-(J1-Pad1)") (class "Default")
      (node (ref "J1") (pin "1") (pinfunction "1_1") (pintype "bidirectional"))
    )
    (net (code "61") (name "unconnected-(J1-Pad6)") (class "Default")
      (node (ref "J1") (pin "6") (pinfunction "6_6") (pintype "bidirectional"))
    )
    (net (code "62") (name "unconnected-(J1-Pad7)") (class "Default")
      (node (ref "J1") (pin "7") (pinfunction "7_7") (pintype "bidirectional"))
    )
    (net (code "63") (name "unconnected-(J2-PadA8)") (class "Default")
      (node (ref "J2") (pin "A8") (pinfunction "A8_A8") (pintype "bidirectional"))
    )
    (net (code "64") (name "unconnected-(J2-PadB8)") (class "Default")
      (node (ref "J2") (pin "B8") (pinfunction "B8_B8") (pintype "bidirectional"))
    )
    (net (code "65") (name "unconnected-(J4-DAT1-PadP8)") (class "Default")
      (node (ref "J4") (pin "P8") (pinfunction "DAT1_P8") (pintype "bidirectional"))
    )
    (net (code "66") (name "unconnected-(J4-DAT2-PadP1)") (class "Default")
      (node (ref "J4") (pin "P1") (pinfunction "DAT2_P1") (pintype "bidirectional"))
    )
    (net (code "67") (name "unconnected-(J4-DETECTION_1-PadS1)") (class "Default")
      (node (ref "J4") (pin "S1") (pinfunction "DETECTION_1_S1") (pintype "bidirectional"))
    )
    (net (code "68") (name "unconnected-(J4-DETECTION_2-PadS2)") (class "Default")
      (node (ref "J4") (pin "S2") (pinfunction "DETECTION_2_S2") (pintype "bidirectional"))
    )
    (net (code "69") (name "unconnected-(U2-NC-Pad22)") (class "Default")
      (node (ref "U2") (pin "22") (pinfunction "NC_22") (pintype "no_connect"))
    )
    (net (code "70") (name "unconnected-(U4-~{ALERT}-Pad5)") (class "Default")
      (node (ref "U4") (pin "5") (pinfunction "~{ALERT}_5") (pintype "output"))
    )
  )
)
